# YellowMotorEncoder.net
KiCad netlist of a schematic drawn in EAGLE
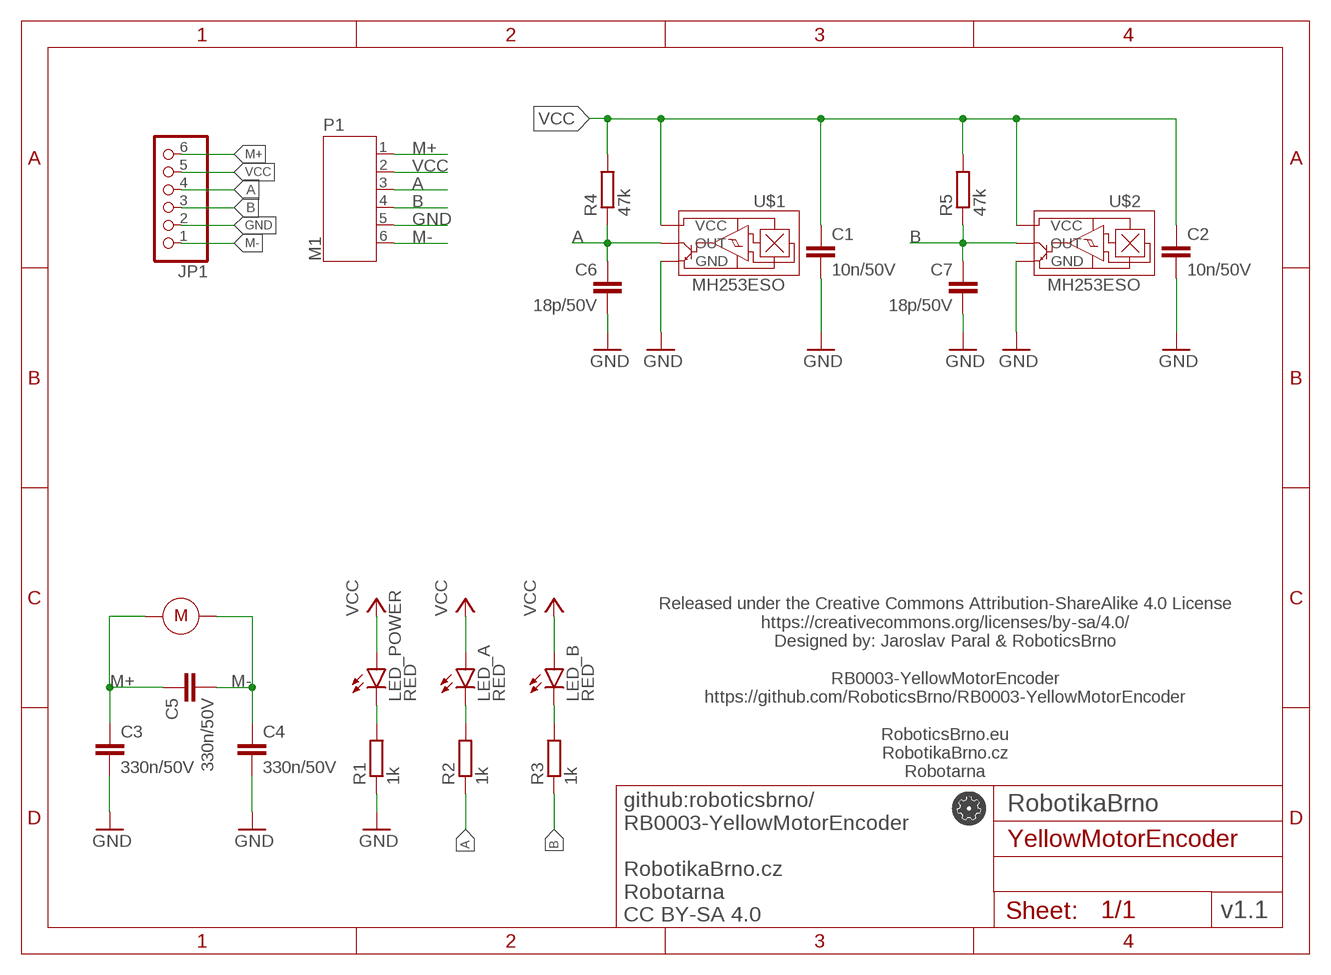
[diagram p0: schematic, sheet 1]

(export (version "E")
  (design (tool "Eeschema 10.0.6"))
  (components
    (comp (ref "C1")
      (value "10n/50V")
      (footprint "eagle-import:C0402")
      (description "MULTILAYER CERAMIC CAPACITORS MLCC - SMD/SMT 10NF 50V 0402 ROHS")
      (fields (field (name "MF") "Samsung Electro-Mechanics"))
      (libsource (lib "eagle-import") (part "C-EUC0402"))
    )
    (comp (ref "C2")
      (value "10n/50V")
      (footprint "eagle-import:C0402")
      (description "MULTILAYER CERAMIC CAPACITORS MLCC - SMD/SMT 10NF 50V 0402 ROHS")
      (fields (field (name "MF") "Samsung Electro-Mechanics"))
      (libsource (lib "eagle-import") (part "C-EUC0402"))
    )
    (comp (ref "C3")
      (value "330n/50V")
      (footprint "eagle-import:C0805")
      (description "MULTILAYER CERAMIC CAPACITORS MLCC - SMD/SMT 330NF 50V 0805 ROHS")
      (fields (field (name "MF") "Guangdong Fenghua Advanced Tech"))
      (libsource (lib "eagle-import") (part "C-EUC0805"))
    )
    (comp (ref "C4")
      (value "330n/50V")
      (footprint "eagle-import:C0805")
      (description "MULTILAYER CERAMIC CAPACITORS MLCC - SMD/SMT 330NF 50V 0805 ROHS")
      (fields (field (name "MF") "Guangdong Fenghua Advanced Tech"))
      (libsource (lib "eagle-import") (part "C-EUC0805"))
    )
    (comp (ref "C5")
      (value "330n/50V")
      (footprint "eagle-import:C0805")
      (description "MULTILAYER CERAMIC CAPACITORS MLCC - SMD/SMT 330NF 50V 0805 ROHS")
      (fields (field (name "MF") "Guangdong Fenghua Advanced Tech"))
      (libsource (lib "eagle-import") (part "C-EUC0805"))
    )
    (comp (ref "C6")
      (value "18p/50V")
      (footprint "eagle-import:C0402")
      (description "MULTILAYER CERAMIC CAPACITORS MLCC - SMD/SMT 18PF 50V 0402 ROHS")
      (fields (field (name "MF") "Guangdong Fenghua Advanced Tech"))
      (libsource (lib "eagle-import") (part "C-EUC0402"))
    )
    (comp (ref "C7")
      (value "18p/50V")
      (footprint "eagle-import:C0402")
      (description "MULTILAYER CERAMIC CAPACITORS MLCC - SMD/SMT 18PF 50V 0402 ROHS")
      (fields (field (name "MF") "Guangdong Fenghua Advanced Tech"))
      (libsource (lib "eagle-import") (part "C-EUC0402"))
    )
    (comp (ref "JP1")
      (value "PINHD-1X6")
      (footprint "eagle-import:1X06")
      (libsource (lib "eagle-import") (part "PINHD-1X6"))
    )
    (comp (ref "LED_A")
      (value "RED")
      (footprint "eagle-import:CHIPLED_0603")
      (description "LIGHT EMITTING DIODES (LED) RED 520~625NM 90~100MCD@20MA TOP VIEW 0603 ROHS")
      (fields (field (name "MF") "Hubei KENTO Elec"))
      (libsource (lib "eagle-import") (part "LEDCHIPLED_0603"))
    )
    (comp (ref "LED_B")
      (value "RED")
      (footprint "eagle-import:CHIPLED_0603")
      (description "LIGHT EMITTING DIODES (LED) RED 520~625NM 90~100MCD@20MA TOP VIEW 0603 ROHS")
      (fields (field (name "MF") "Hubei KENTO Elec"))
      (libsource (lib "eagle-import") (part "LEDCHIPLED_0603"))
    )
    (comp (ref "LED_POWER")
      (value "RED")
      (footprint "eagle-import:CHIPLED_0603")
      (description "LIGHT EMITTING DIODES (LED) RED 520~625NM 90~100MCD@20MA TOP VIEW 0603 ROHS")
      (fields (field (name "MF") "Hubei KENTO Elec"))
      (libsource (lib "eagle-import") (part "LEDCHIPLED_0603"))
    )
    (comp (ref "P1")
      (value "M1")
      (footprint "eagle-import:JST-PH6")
      (libsource (lib "eagle-import") (part "JST-PH6"))
    )
    (comp (ref "R1")
      (value "1k")
      (footprint "eagle-import:R0603")
      (description "CHIP RESISTOR - SURFACE MOUNT 1KOHMS ±1% 1/10W 0603 ROHS")
      (fields (field (name "MF") "Uniroyal Elec"))
      (libsource (lib "eagle-import") (part "R-EU_R0603"))
    )
    (comp (ref "R2")
      (value "1k")
      (footprint "eagle-import:R0603")
      (description "CHIP RESISTOR - SURFACE MOUNT 1KOHMS ±1% 1/10W 0603 ROHS")
      (fields (field (name "MF") "Uniroyal Elec"))
      (libsource (lib "eagle-import") (part "R-EU_R0603"))
    )
    (comp (ref "R3")
      (value "1k")
      (footprint "eagle-import:R0603")
      (description "CHIP RESISTOR - SURFACE MOUNT 1KOHMS ±1% 1/10W 0603 ROHS")
      (fields (field (name "MF") "Uniroyal Elec"))
      (libsource (lib "eagle-import") (part "R-EU_R0603"))
    )
    (comp (ref "R4")
      (value "47k")
      (footprint "eagle-import:R0603")
      (description "CHIP RESISTOR - SURFACE MOUNT 47KOHMS ±1% 1/10W 0603 ROHS")
      (fields (field (name "MF") "Uniroyal Elec"))
      (libsource (lib "eagle-import") (part "R-EU_R0603"))
    )
    (comp (ref "R5")
      (value "47k")
      (footprint "eagle-import:R0603")
      (description "CHIP RESISTOR - SURFACE MOUNT 47KOHMS ±1% 1/10W 0603 ROHS")
      (fields (field (name "MF") "Uniroyal Elec"))
      (libsource (lib "eagle-import") (part "R-EU_R0603"))
    )
    (comp (ref "U$1")
      (value "MH253ESO")
      (footprint "eagle-import:SOT23")
      (fields (field (name "MF") "Magnesensor Tech (MST)"))
      (libsource (lib "eagle-import") (part "MH253ESO"))
    )
    (comp (ref "U$2")
      (value "MH253ESO")
      (footprint "eagle-import:SOT23")
      (fields (field (name "MF") "Magnesensor Tech (MST)"))
      (libsource (lib "eagle-import") (part "MH253ESO"))
    )
    (comp (ref "U$3")
      (value "YELLOW_MOTOR")
      (footprint "eagle-import:YELLOW_MOTOR")
      (libsource (lib "eagle-import") (part "YELLOW_MOTOR"))
    )
  )
  (nets
    (net (code "1") (name "A") (class "Default")
      (node (ref "C6") (pin "1") (pinfunction "1_1") (pintype "passive"))
      (node (ref "JP1") (pin "4") (pinfunction "4_4") (pintype "passive"))
      (node (ref "P1") (pin "3") (pinfunction "3_3") (pintype "passive"))
      (node (ref "R2") (pin "1") (pinfunction "1_1") (pintype "passive"))
      (node (ref "R4") (pin "1") (pinfunction "1_1") (pintype "passive"))
      (node (ref "U$1") (pin "2") (pinfunction "OUT_2") (pintype "open_collector"))
    )
    (net (code "2") (name "B") (class "Default")
      (node (ref "C7") (pin "1") (pinfunction "1_1") (pintype "passive"))
      (node (ref "JP1") (pin "3") (pinfunction "3_3") (pintype "passive"))
      (node (ref "P1") (pin "4") (pinfunction "4_4") (pintype "passive"))
      (node (ref "R3") (pin "1") (pinfunction "1_1") (pintype "passive"))
      (node (ref "R5") (pin "1") (pinfunction "1_1") (pintype "passive"))
      (node (ref "U$2") (pin "2") (pinfunction "OUT_2") (pintype "open_collector"))
    )
    (net (code "3") (name "GND") (class "Default")
      (node (ref "C1") (pin "2") (pinfunction "2_2") (pintype "passive"))
      (node (ref "C2") (pin "2") (pinfunction "2_2") (pintype "passive"))
      (node (ref "C3") (pin "2") (pinfunction "2_2") (pintype "passive"))
      (node (ref "C4") (pin "2") (pinfunction "2_2") (pintype "passive"))
      (node (ref "C6") (pin "2") (pinfunction "2_2") (pintype "passive"))
      (node (ref "C7") (pin "2") (pinfunction "2_2") (pintype "passive"))
      (node (ref "JP1") (pin "2") (pinfunction "2_2") (pintype "passive"))
      (node (ref "P1") (pin "5") (pinfunction "5_5") (pintype "passive"))
      (node (ref "R1") (pin "1") (pinfunction "1_1") (pintype "passive"))
      (node (ref "U$1") (pin "3") (pinfunction "GND_3") (pintype "power_in"))
      (node (ref "U$2") (pin "3") (pinfunction "GND_3") (pintype "power_in"))
    )
    (net (code "4") (name "M+") (class "Default")
      (node (ref "C3") (pin "1") (pinfunction "1_1") (pintype "passive"))
      (node (ref "C5") (pin "1") (pinfunction "1_1") (pintype "passive"))
      (node (ref "JP1") (pin "6") (pinfunction "6_6") (pintype "passive"))
      (node (ref "P1") (pin "1") (pinfunction "1_1") (pintype "passive"))
      (node (ref "U$3") (pin "P$2") (pinfunction "P$2_P$2") (pintype "passive"))
    )
    (net (code "5") (name "M-") (class "Default")
      (node (ref "C4") (pin "1") (pinfunction "1_1") (pintype "passive"))
      (node (ref "C5") (pin "2") (pinfunction "2_2") (pintype "passive"))
      (node (ref "JP1") (pin "1") (pinfunction "1_1") (pintype "passive"))
      (node (ref "P1") (pin "6") (pinfunction "6_6") (pintype "passive"))
      (node (ref "U$3") (pin "P$1") (pinfunction "P$1_P$1") (pintype "passive"))
    )
    (net (code "6") (name "Net-(LED_A-PadC)") (class "Default")
      (node (ref "LED_A") (pin "C") (pinfunction "C_C") (pintype "passive"))
      (node (ref "R2") (pin "2") (pinfunction "2_2") (pintype "passive"))
    )
    (net (code "7") (name "Net-(LED_B-PadC)") (class "Default")
      (node (ref "LED_B") (pin "C") (pinfunction "C_C") (pintype "passive"))
      (node (ref "R3") (pin "2") (pinfunction "2_2") (pintype "passive"))
    )
    (net (code "8") (name "Net-(LED_POWER-PadC)") (class "Default")
      (node (ref "LED_POWER") (pin "C") (pinfunction "C_C") (pintype "passive"))
      (node (ref "R1") (pin "2") (pinfunction "2_2") (pintype "passive"))
    )
    (net (code "9") (name "VCC") (class "Default")
      (node (ref "C1") (pin "1") (pinfunction "1_1") (pintype "passive"))
      (node (ref "C2") (pin "1") (pinfunction "1_1") (pintype "passive"))
      (node (ref "JP1") (pin "5") (pinfunction "5_5") (pintype "passive"))
      (node (ref "LED_A") (pin "A") (pinfunction "A_A") (pintype "passive"))
      (node (ref "LED_B") (pin "A") (pinfunction "A_A") (pintype "passive"))
      (node (ref "LED_POWER") (pin "A") (pinfunction "A_A") (pintype "passive"))
      (node (ref "P1") (pin "2") (pinfunction "2_2") (pintype "passive"))
      (node (ref "R4") (pin "2") (pinfunction "2_2") (pintype "passive"))
      (node (ref "R5") (pin "2") (pinfunction "2_2") (pintype "passive"))
      (node (ref "U$1") (pin "1") (pinfunction "VCC_1") (pintype "power_in"))
      (node (ref "U$2") (pin "1") (pinfunction "VCC_1") (pintype "power_in"))
    )
  )
)
